# RelayBoard.net
KiCad netlist of a schematic drawn in EAGLE
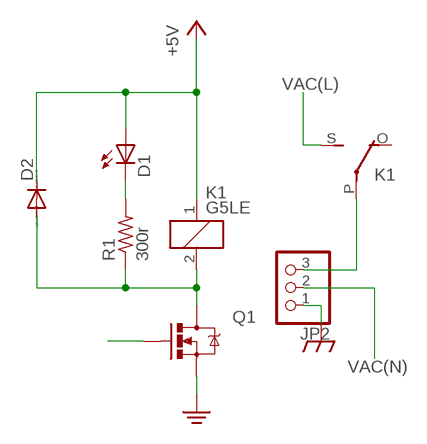
[diagram p0: schematic, sheet 1]

(export (version "E")
  (design (tool "Eeschema 10.0.6"))
  (components
    (comp (ref "D1")
      (value "U57X32")
      (footprint "eagle-import:U57X32")
      (libsource (lib "eagle-import") (part "U57X32"))
    )
    (comp (ref "D2")
      (value "1N4004")
      (footprint "eagle-import:DO41-10")
      (libsource (lib "eagle-import") (part "1N4004"))
    )
    (comp (ref "JP2")
      (value "PINHD-1X3")
      (footprint "eagle-import:1X03")
      (libsource (lib "eagle-import") (part "PINHD-1X3"))
    )
    (comp (ref "K1")
      (value "G5LE")
      (footprint "eagle-import:G5LE")
      (libsource (lib "eagle-import") (part "G5LE"))
    )
    (comp (ref "Q1")
      (value "MOSFET-NCHANNELSMD")
      (footprint "eagle-import:SOT23-3")
      (libsource (lib "eagle-import") (part "MOSFET-NCHANNELSMD"))
    )
    (comp (ref "R1")
      (value "300r")
      (footprint "eagle-import:R0603")
      (libsource (lib "eagle-import") (part "R-US_R0603"))
    )
  )
  (nets
    (net (code "1") (name "+5V") (class "Default")
      (node (ref "D1") (pin "A") (pinfunction "A_A") (pintype "passive"))
      (node (ref "D2") (pin "C") (pinfunction "C_C") (pintype "passive"))
      (node (ref "K1") (pin "1") (pinfunction "1_1") (pintype "passive"))
    )
    (net (code "2") (name "/VAC(L)") (class "Default")
      (node (ref "K1") (pin "S") (pinfunction "S_S") (pintype "passive"))
    )
    (net (code "3") (name "/VAC(N)") (class "Default")
      (node (ref "JP2") (pin "2") (pinfunction "2_2") (pintype "passive"))
    )
    (net (code "4") (name "Net-(D1-C)") (class "Default")
      (node (ref "D1") (pin "K") (pinfunction "C_K") (pintype "passive"))
      (node (ref "R1") (pin "2") (pinfunction "2_2") (pintype "passive"))
    )
    (net (code "5") (name "Net-(JP2-Pad3)") (class "Default")
      (node (ref "JP2") (pin "3") (pinfunction "3_3") (pintype "passive"))
      (node (ref "K1") (pin "P") (pinfunction "P_P") (pintype "passive"))
    )
    (net (code "6") (name "Net-(Q1-D)") (class "Default")
      (node (ref "D2") (pin "A") (pinfunction "A_A") (pintype "passive"))
      (node (ref "K1") (pin "2") (pinfunction "2_2") (pintype "passive"))
      (node (ref "Q1") (pin "3") (pinfunction "D_3") (pintype "passive"))
      (node (ref "R1") (pin "1") (pinfunction "1_1") (pintype "passive"))
    )
    (net (code "7") (name "PE") (class "Default")
      (node (ref "Q1") (pin "2") (pinfunction "S_2") (pintype "passive"))
    )
    (net (code "8") (name "PGND") (class "Default")
      (node (ref "JP2") (pin "1") (pinfunction "1_1") (pintype "passive"))
    )
    (net (code "9") (name "unconnected-(K1-PadO)") (class "Default")
      (node (ref "K1") (pin "O") (pinfunction "O_O") (pintype "passive"))
    )
    (net (code "10") (name "unconnected-(Q1-G-Pad1)") (class "Default")
      (node (ref "Q1") (pin "1") (pinfunction "G_1") (pintype "passive"))
    )
  )
)
